# Tactical_LED_Light.net
KiCad netlist of a schematic drawn in Altium Designer
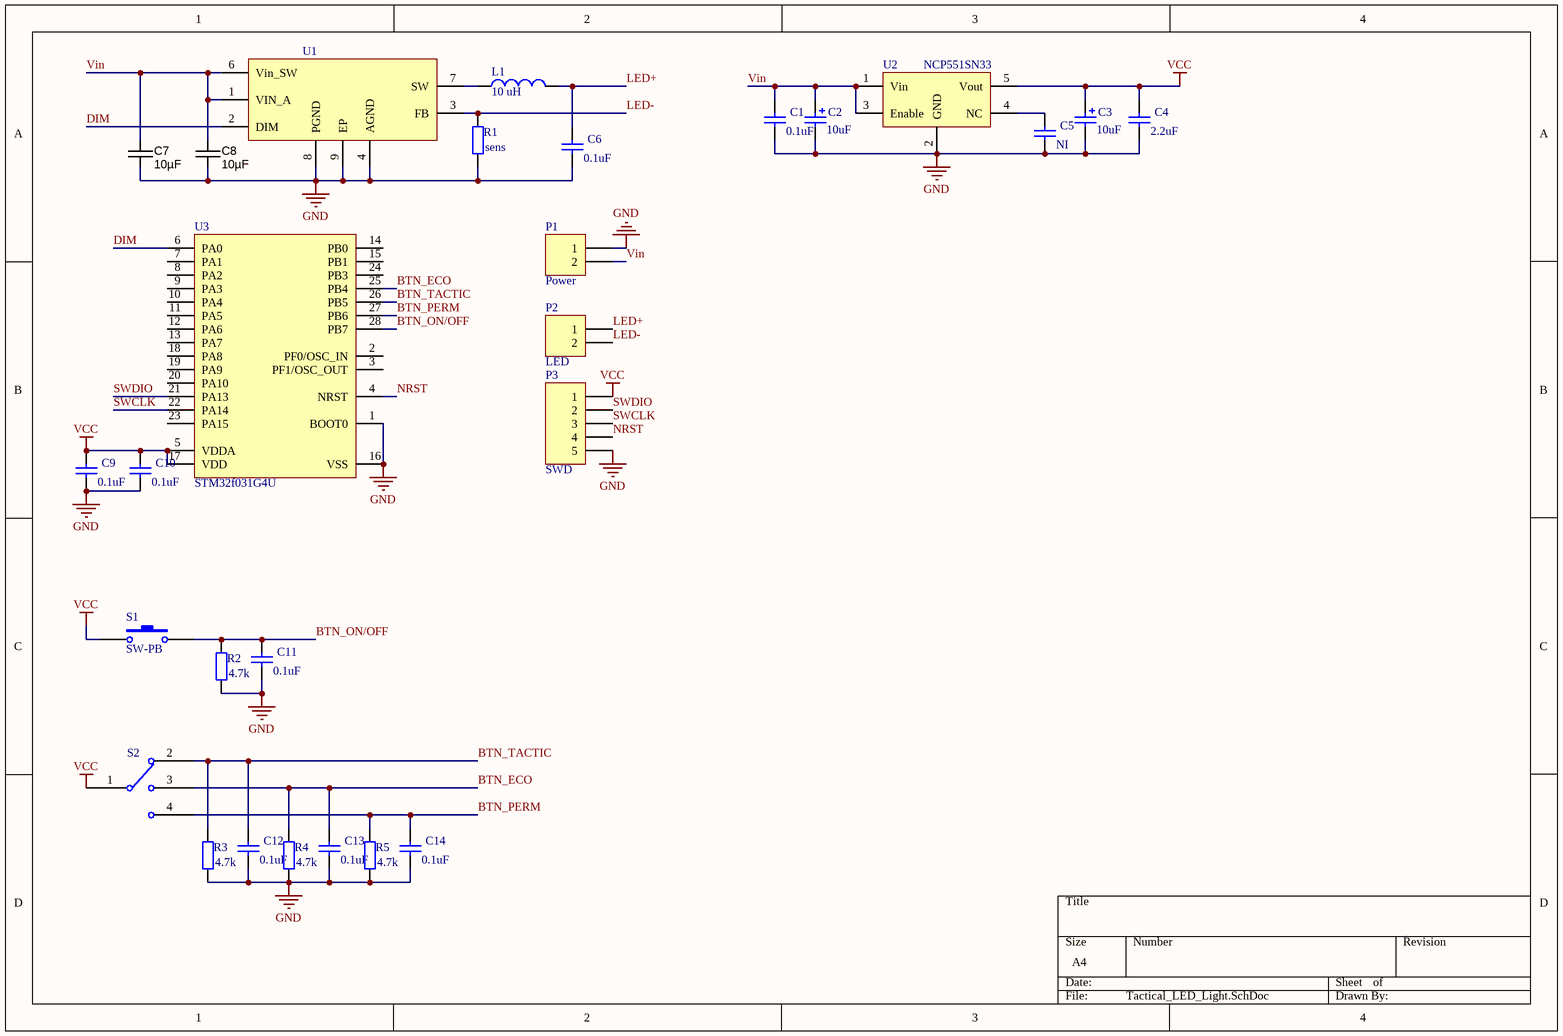
[diagram p0: Tactical_LED_Light.SchDoc]

(export (version "E")
  (design (tool "Eeschema 10.0.6"))
  (components
    (comp (ref "C1")
      (value "0.1uF")
      (footprint "CAPC1608X90N")
      (description "Capacitor")
      (fields (field (name "Comment") "Cap") (field (name "PUBLISHER") "Altium Limited"))
      (libsource (lib "Miscellaneous Devices") (part "Cap"))
    )
    (comp (ref "C2")
      (value "10uF")
      (footprint "CAPMP3528X210N")
      (description "Polarized Capacitor (Axial)")
      (fields (field (name "Comment") "Cap Pol2") (field (name "PUBLISHER") "Altium Limited"))
      (libsource (lib "Miscellaneous Devices") (part "Cap Pol2"))
    )
    (comp (ref "C3")
      (value "10uF")
      (footprint "CAPMP3528X210N")
      (description "Polarized Capacitor (Axial)")
      (fields (field (name "Comment") "Cap Pol2") (field (name "PUBLISHER") "Altium Limited"))
      (libsource (lib "Miscellaneous Devices") (part "Cap Pol2"))
    )
    (comp (ref "C4")
      (value "2.2uF")
      (footprint "CAPC1608X90N")
      (description "Capacitor")
      (fields (field (name "Comment") "Cap") (field (name "PUBLISHER") "Altium Limited"))
      (libsource (lib "Miscellaneous Devices") (part "Cap"))
    )
    (comp (ref "C5")
      (value "NI")
      (footprint "CAPC1608X90N")
      (description "Capacitor")
      (fields (field (name "Comment") "Cap") (field (name "PUBLISHER") "Altium Limited"))
      (libsource (lib "Miscellaneous Devices") (part "Cap"))
    )
    (comp (ref "C6")
      (value "0.1uF")
      (footprint "CAPC1608X90N")
      (description "Capacitor")
      (fields (field (name "Comment") "Cap") (field (name "PUBLISHER") "Altium Limited"))
      (libsource (lib "Miscellaneous Devices") (part "Cap"))
    )
    (comp (ref "C7")
      (value "10µF")
      (footprint "CAPC3216X100N")
      (description "Capacitor SMD Cer 10uF 20% 16V X5R 1210")
      (fields (field (name "TOLERANCE") "±20%"))
      (libsource (lib "PBL - Capacitors") (part "CAPC_10u_1210_50V"))
    )
    (comp (ref "C8")
      (value "10µF")
      (footprint "CAPC3216X100N")
      (description "Capacitor SMD Cer 10uF 20% 16V X5R 1210")
      (fields (field (name "TOLERANCE") "±20%"))
      (libsource (lib "PBL - Capacitors") (part "CAPC_10u_1210_50V"))
    )
    (comp (ref "C9")
      (value "0.1uF")
      (footprint "CAPC1608X90N")
      (description "Capacitor")
      (fields (field (name "Comment") "Cap") (field (name "PUBLISHER") "Altium Limited"))
      (libsource (lib "Miscellaneous Devices") (part "Cap"))
    )
    (comp (ref "C10")
      (value "0.1uF")
      (footprint "CAPC1608X90N")
      (description "Capacitor")
      (fields (field (name "Comment") "Cap") (field (name "PUBLISHER") "Altium Limited"))
      (libsource (lib "Miscellaneous Devices") (part "Cap"))
    )
    (comp (ref "C11")
      (value "0.1uF")
      (footprint "CAPC1608X90N")
      (description "Capacitor")
      (fields (field (name "Comment") "Cap") (field (name "PUBLISHER") "Altium Limited"))
      (libsource (lib "Miscellaneous Devices") (part "Cap"))
    )
    (comp (ref "C12")
      (value "0.1uF")
      (footprint "CAPC1608X90N")
      (description "Capacitor")
      (fields (field (name "Comment") "Cap") (field (name "PUBLISHER") "Altium Limited"))
      (libsource (lib "Miscellaneous Devices") (part "Cap"))
    )
    (comp (ref "C13")
      (value "0.1uF")
      (footprint "CAPC1608X90N")
      (description "Capacitor")
      (fields (field (name "Comment") "Cap") (field (name "PUBLISHER") "Altium Limited"))
      (libsource (lib "Miscellaneous Devices") (part "Cap"))
    )
    (comp (ref "C14")
      (value "0.1uF")
      (footprint "CAPC1608X90N")
      (description "Capacitor")
      (fields (field (name "Comment") "Cap") (field (name "PUBLISHER") "Altium Limited"))
      (libsource (lib "Miscellaneous Devices") (part "Cap"))
    )
    (comp (ref "L1")
      (value "10 uH")
      (footprint "IND_CRDH123")
      (description "CDRH125NP-100MC")
      (fields (field (name "Comment") "Inductor") (field (name "PUBLISHER") "Altium Limited"))
      (libsource (lib "Miscellaneous Devices") (part "Inductor"))
    )
    (comp (ref "P1")
      (value "Power")
      (footprint "HDR1X2")
      (description "Header, 2-Pin")
      (fields (field (name "PUBLISHER") "Altium Limited"))
      (libsource (lib "Miscellaneous Connectors") (part "Header 2"))
    )
    (comp (ref "P2")
      (value "LED")
      (footprint "HDR_1x2")
      (description "Header, 2-Pin")
      (fields (field (name "PUBLISHER") "Altium Limited"))
      (libsource (lib "Miscellaneous Connectors") (part "Header 2"))
    )
    (comp (ref "P3")
      (value "SWD")
      (footprint "HDR1X5")
      (description "Header, 5-Pin")
      (fields (field (name "PUBLISHER") "Altium Limited"))
      (libsource (lib "Miscellaneous Connectors") (part "Header 5"))
    )
    (comp (ref "R1")
      (value "sens")
      (footprint "RESC6332X70N")
      (description "Resistor")
      (fields (field (name "Comment") "Res2") (field (name "PUBLISHER") "Altium Limited"))
      (libsource (lib "Miscellaneous Devices") (part "Res2"))
    )
    (comp (ref "R2")
      (value "4.7k")
      (footprint "RESC1608X55N")
      (description "Resistor")
      (fields (field (name "Comment") "Res2") (field (name "PUBLISHER") "Altium Limited"))
      (libsource (lib "Miscellaneous Devices") (part "Res2"))
    )
    (comp (ref "R3")
      (value "4.7k")
      (footprint "RESC1608X55N")
      (description "Resistor")
      (fields (field (name "Comment") "Res2") (field (name "PUBLISHER") "Altium Limited"))
      (libsource (lib "Miscellaneous Devices") (part "Res2"))
    )
    (comp (ref "R4")
      (value "4.7k")
      (footprint "RESC1608X55N")
      (description "Resistor")
      (fields (field (name "Comment") "Res2") (field (name "PUBLISHER") "Altium Limited"))
      (libsource (lib "Miscellaneous Devices") (part "Res2"))
    )
    (comp (ref "R5")
      (value "4.7k")
      (footprint "RESC1608X55N")
      (description "Resistor")
      (fields (field (name "Comment") "Res2") (field (name "PUBLISHER") "Altium Limited"))
      (libsource (lib "Miscellaneous Devices") (part "Res2"))
    )
    (comp (ref "S1")
      (value "SW-PB")
      (footprint "HDR1X2")
      (description "Switch")
      (fields (field (name "PUBLISHER") "Altium Limited"))
      (libsource (lib "Miscellaneous Devices") (part "SW-PB"))
    )
    (comp (ref "S2")
      (value "3-Pos Switch")
      (footprint "TSSM1032C3")
      (description "3 position switch")
      (libsource (lib "Tactical_LED_Light") (part "3-Pos Switch"))
    )
    (comp (ref "U1")
      (value "LED2001")
      (footprint "LED2001")
      (description "LED Driver 4A")
      (libsource (lib "Tactical_LED_Light") (part "LED2001"))
    )
    (comp (ref "U2") (value "NCP551SN33") (libsource (lib "Tactical_LED_Light") (part "NCP551SN33")))
    (comp (ref "U3")
      (value "STM32f031G4U")
      (footprint "Quad28")
      (description "UFQFPN28")
      (libsource (lib "Tactical_LED_Light") (part "STM32f031G4U"))
    )
  )
  (nets
    (net (code "1") (name "/BTN_ECO") (class "Default")
      (node (ref "C13") (pin "2") (pinfunction "2_2") (pintype "passive"))
      (node (ref "R4") (pin "2") (pinfunction "2_2") (pintype "passive"))
      (node (ref "S2") (pin "3") (pinfunction "3_3") (pintype "passive"))
      (node (ref "U3") (pin "25") (pinfunction "PB4_25") (pintype "passive"))
    )
    (net (code "2") (name "/BTN_ON{slash}OFF") (class "Default")
      (node (ref "C11") (pin "2") (pinfunction "2_2") (pintype "passive"))
      (node (ref "R2") (pin "2") (pinfunction "2_2") (pintype "passive"))
      (node (ref "S1") (pin "2") (pinfunction "2_2") (pintype "passive"))
      (node (ref "U3") (pin "28") (pinfunction "PB7_28") (pintype "passive"))
    )
    (net (code "3") (name "/BTN_PERM") (class "Default")
      (node (ref "C14") (pin "2") (pinfunction "2_2") (pintype "passive"))
      (node (ref "R5") (pin "2") (pinfunction "2_2") (pintype "passive"))
      (node (ref "S2") (pin "4") (pinfunction "4_4") (pintype "passive"))
      (node (ref "U3") (pin "27") (pinfunction "PB6_27") (pintype "passive"))
    )
    (net (code "4") (name "/BTN_TACTIC") (class "Default")
      (node (ref "C12") (pin "2") (pinfunction "2_2") (pintype "passive"))
      (node (ref "R3") (pin "2") (pinfunction "2_2") (pintype "passive"))
      (node (ref "S2") (pin "2") (pinfunction "2_2") (pintype "passive"))
      (node (ref "U3") (pin "26") (pinfunction "PB5_26") (pintype "passive"))
    )
    (net (code "5") (name "/DIM") (class "Default")
      (node (ref "U1") (pin "2") (pinfunction "DIM_2") (pintype "passive"))
      (node (ref "U3") (pin "6") (pinfunction "PA0_6") (pintype "passive"))
    )
    (net (code "6") (name "/LED+") (class "Default")
      (node (ref "C6") (pin "2") (pinfunction "2_2") (pintype "passive"))
      (node (ref "L1") (pin "2") (pinfunction "2_2") (pintype "passive"))
      (node (ref "P2") (pin "1") (pinfunction "1_1") (pintype "passive"))
    )
    (net (code "7") (name "/LED-") (class "Default")
      (node (ref "P2") (pin "2") (pinfunction "2_2") (pintype "passive"))
      (node (ref "R1") (pin "2") (pinfunction "2_2") (pintype "passive"))
      (node (ref "U1") (pin "3") (pinfunction "FB_3") (pintype "passive"))
    )
    (net (code "8") (name "/NRST") (class "Default")
      (node (ref "P3") (pin "4") (pinfunction "4_4") (pintype "passive"))
      (node (ref "U3") (pin "4") (pinfunction "NRST_4") (pintype "passive"))
    )
    (net (code "9") (name "/SWCLK") (class "Default")
      (node (ref "P3") (pin "3") (pinfunction "3_3") (pintype "passive"))
      (node (ref "U3") (pin "22") (pinfunction "PA14_22") (pintype "passive"))
    )
    (net (code "10") (name "/SWDIO") (class "Default")
      (node (ref "P3") (pin "2") (pinfunction "2_2") (pintype "passive"))
      (node (ref "U3") (pin "21") (pinfunction "PA13_21") (pintype "passive"))
    )
    (net (code "11") (name "/Vin") (class "Default")
      (node (ref "C1") (pin "2") (pinfunction "2_2") (pintype "passive"))
      (node (ref "C2") (pin "1") (pinfunction "1_1") (pintype "passive"))
      (node (ref "C7") (pin "1") (pintype "passive"))
      (node (ref "C8") (pin "1") (pintype "passive"))
      (node (ref "P1") (pin "2") (pinfunction "2_2") (pintype "passive"))
      (node (ref "U1") (pin "1") (pinfunction "VIN_A_1") (pintype "passive"))
      (node (ref "U1") (pin "6") (pinfunction "Vin_SW_6") (pintype "passive"))
      (node (ref "U2") (pin "1") (pinfunction "Vin_1") (pintype "passive"))
      (node (ref "U2") (pin "3") (pinfunction "Enable_3") (pintype "passive"))
    )
    (net (code "12") (name "GND") (class "Default")
      (node (ref "C1") (pin "1") (pinfunction "1_1") (pintype "passive"))
      (node (ref "C10") (pin "1") (pinfunction "1_1") (pintype "passive"))
      (node (ref "C11") (pin "1") (pinfunction "1_1") (pintype "passive"))
      (node (ref "C12") (pin "1") (pinfunction "1_1") (pintype "passive"))
      (node (ref "C13") (pin "1") (pinfunction "1_1") (pintype "passive"))
      (node (ref "C14") (pin "1") (pinfunction "1_1") (pintype "passive"))
      (node (ref "C2") (pin "2") (pinfunction "2_2") (pintype "passive"))
      (node (ref "C3") (pin "2") (pinfunction "2_2") (pintype "passive"))
      (node (ref "C4") (pin "1") (pinfunction "1_1") (pintype "passive"))
      (node (ref "C5") (pin "1") (pinfunction "1_1") (pintype "passive"))
      (node (ref "C6") (pin "1") (pinfunction "1_1") (pintype "passive"))
      (node (ref "C7") (pin "2") (pintype "passive"))
      (node (ref "C8") (pin "2") (pintype "passive"))
      (node (ref "C9") (pin "1") (pinfunction "1_1") (pintype "passive"))
      (node (ref "P1") (pin "1") (pinfunction "1_1") (pintype "passive"))
      (node (ref "P3") (pin "5") (pinfunction "5_5") (pintype "passive"))
      (node (ref "R1") (pin "1") (pinfunction "1_1") (pintype "passive"))
      (node (ref "R2") (pin "1") (pinfunction "1_1") (pintype "passive"))
      (node (ref "R3") (pin "1") (pinfunction "1_1") (pintype "passive"))
      (node (ref "R4") (pin "1") (pinfunction "1_1") (pintype "passive"))
      (node (ref "R5") (pin "1") (pinfunction "1_1") (pintype "passive"))
      (node (ref "U1") (pin "4") (pinfunction "AGND_4") (pintype "passive"))
      (node (ref "U1") (pin "8") (pinfunction "PGND_8") (pintype "passive"))
      (node (ref "U1") (pin "9") (pinfunction "EP_9") (pintype "passive"))
      (node (ref "U2") (pin "2") (pinfunction "GND_2") (pintype "passive"))
      (node (ref "U3") (pin "1") (pinfunction "BOOT0_1") (pintype "passive"))
      (node (ref "U3") (pin "16") (pinfunction "VSS_16") (pintype "passive"))
    )
    (net (code "13") (name "Net-(U1-SW)") (class "Default")
      (node (ref "L1") (pin "1") (pinfunction "1_1") (pintype "passive"))
      (node (ref "U1") (pin "7") (pinfunction "SW_7") (pintype "passive"))
    )
    (net (code "14") (name "Net-(U2-NC)") (class "Default")
      (node (ref "C5") (pin "2") (pinfunction "2_2") (pintype "passive"))
      (node (ref "U2") (pin "4") (pinfunction "NC_4") (pintype "passive"))
    )
    (net (code "15") (name "VCC") (class "Default")
      (node (ref "C10") (pin "2") (pinfunction "2_2") (pintype "passive"))
      (node (ref "C3") (pin "1") (pinfunction "1_1") (pintype "passive"))
      (node (ref "C4") (pin "2") (pinfunction "2_2") (pintype "passive"))
      (node (ref "C9") (pin "2") (pinfunction "2_2") (pintype "passive"))
      (node (ref "P3") (pin "1") (pinfunction "1_1") (pintype "passive"))
      (node (ref "S1") (pin "1") (pinfunction "1_1") (pintype "passive"))
      (node (ref "S2") (pin "1") (pinfunction "1_1") (pintype "passive"))
      (node (ref "U2") (pin "5") (pinfunction "Vout_5") (pintype "passive"))
      (node (ref "U3") (pin "17") (pinfunction "VDD_17") (pintype "passive"))
      (node (ref "U3") (pin "5") (pinfunction "VDDA_5") (pintype "passive"))
    )
    (net (code "16") (name "unconnected-(U3-PA1-Pad7)") (class "Default")
      (node (ref "U3") (pin "7") (pinfunction "PA1_7") (pintype "passive"))
    )
    (net (code "17") (name "unconnected-(U3-PA2-Pad8)") (class "Default")
      (node (ref "U3") (pin "8") (pinfunction "PA2_8") (pintype "passive"))
    )
    (net (code "18") (name "unconnected-(U3-PA3-Pad9)") (class "Default")
      (node (ref "U3") (pin "9") (pinfunction "PA3_9") (pintype "passive"))
    )
    (net (code "19") (name "unconnected-(U3-PA4-Pad10)") (class "Default")
      (node (ref "U3") (pin "10") (pinfunction "PA4_10") (pintype "passive"))
    )
    (net (code "20") (name "unconnected-(U3-PA5-Pad11)") (class "Default")
      (node (ref "U3") (pin "11") (pinfunction "PA5_11") (pintype "passive"))
    )
    (net (code "21") (name "unconnected-(U3-PA6-Pad12)") (class "Default")
      (node (ref "U3") (pin "12") (pinfunction "PA6_12") (pintype "passive"))
    )
    (net (code "22") (name "unconnected-(U3-PA7-Pad13)") (class "Default")
      (node (ref "U3") (pin "13") (pinfunction "PA7_13") (pintype "passive"))
    )
    (net (code "23") (name "unconnected-(U3-PA8-Pad18)") (class "Default")
      (node (ref "U3") (pin "18") (pinfunction "PA8_18") (pintype "passive"))
    )
    (net (code "24") (name "unconnected-(U3-PA9-Pad19)") (class "Default")
      (node (ref "U3") (pin "19") (pinfunction "PA9_19") (pintype "passive"))
    )
    (net (code "25") (name "unconnected-(U3-PA10-Pad20)") (class "Default")
      (node (ref "U3") (pin "20") (pinfunction "PA10_20") (pintype "passive"))
    )
    (net (code "26") (name "unconnected-(U3-PA15-Pad23)") (class "Default")
      (node (ref "U3") (pin "23") (pinfunction "PA15_23") (pintype "passive"))
    )
    (net (code "27") (name "unconnected-(U3-PB0-Pad14)") (class "Default")
      (node (ref "U3") (pin "14") (pinfunction "PB0_14") (pintype "passive"))
    )
    (net (code "28") (name "unconnected-(U3-PB1-Pad15)") (class "Default")
      (node (ref "U3") (pin "15") (pinfunction "PB1_15") (pintype "passive"))
    )
    (net (code "29") (name "unconnected-(U3-PB3-Pad24)") (class "Default")
      (node (ref "U3") (pin "24") (pinfunction "PB3_24") (pintype "passive"))
    )
    (net (code "30") (name "unconnected-(U3-PF0{slash}OSC_IN-Pad2)") (class "Default")
      (node (ref "U3") (pin "2") (pinfunction "PF0/OSC_IN_2") (pintype "passive"))
    )
    (net (code "31") (name "unconnected-(U3-PF1{slash}OSC_OUT-Pad3)") (class "Default")
      (node (ref "U3") (pin "3") (pinfunction "PF1/OSC_OUT_3") (pintype "passive"))
    )
  )
)
